# Adafruit_PCF8523_RTC_HVSON.net
KiCad netlist of a schematic drawn in EAGLE
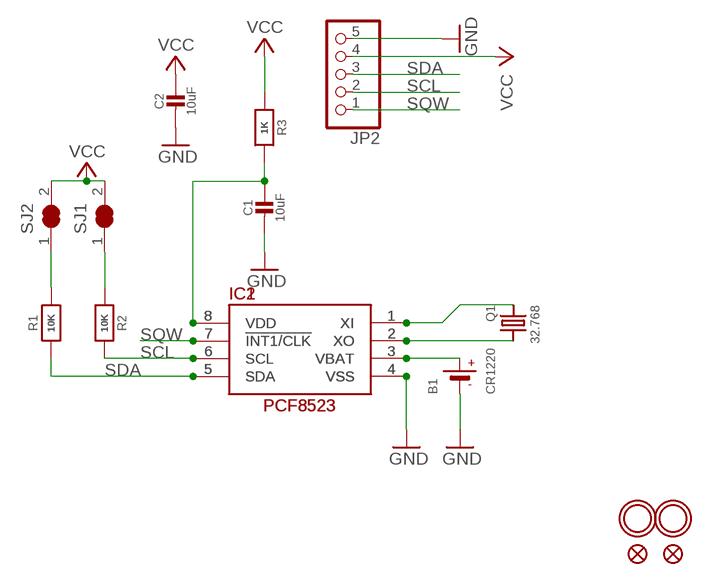
[diagram p0: schematic, sheet 1]

(export (version "E")
  (design (tool "Eeschema 10.0.6"))
  (components
    (comp (ref "B1")
      (value "CR1220")
      (footprint "eagle-import:CR1220")
      (libsource (lib "eagle-import") (part "BATTERYCR1220_SMT"))
    )
    (comp (ref "C1")
      (value "10uF")
      (footprint "eagle-import:0805-NO")
      (libsource (lib "eagle-import") (part "CAP_CERAMIC0805-NOOUTLINE"))
    )
    (comp (ref "C2")
      (value "10uF")
      (footprint "eagle-import:0805-NO")
      (libsource (lib "eagle-import") (part "CAP_CERAMIC0805-NOOUTLINE"))
    )
    (comp (ref "FID1")
      (value "FIDUCIAL_1MM")
      (footprint "eagle-import:FIDUCIAL_1MM")
      (libsource (lib "eagle-import") (part "FIDUCIAL_1MM"))
    )
    (comp (ref "FID2")
      (value "FIDUCIAL_1MM")
      (footprint "eagle-import:FIDUCIAL_1MM")
      (libsource (lib "eagle-import") (part "FIDUCIAL_1MM"))
    )
    (comp (ref "IC1")
      (value "RTC_PCF8523/T")
      (footprint "eagle-import:SOIC8_150MIL")
      (libsource (lib "eagle-import") (part "RTC_PCF8523/T"))
    )
    (comp (ref "IC2")
      (value "RTC_PCF8523/TK")
      (footprint "eagle-import:HVSON8_4X4")
      (libsource (lib "eagle-import") (part "RTC_PCF8523/TK"))
    )
    (comp (ref "JP2")
      (value "HEADER-1X576MIL")
      (footprint "eagle-import:1X05_ROUND_76")
      (libsource (lib "eagle-import") (part "HEADER-1X576MIL"))
    )
    (comp (ref "Q1")
      (value "32.768")
      (footprint "eagle-import:XTAL3215")
      (libsource (lib "eagle-import") (part "CRYSTAL_3215"))
    )
    (comp (ref "R1")
      (value "10K")
      (footprint "eagle-import:0805-NO")
      (libsource (lib "eagle-import") (part "RESISTOR0805_NOOUTLINE"))
    )
    (comp (ref "R2")
      (value "10K")
      (footprint "eagle-import:0805-NO")
      (libsource (lib "eagle-import") (part "RESISTOR0805_NOOUTLINE"))
    )
    (comp (ref "R3")
      (value "1K")
      (footprint "eagle-import:0805-NO")
      (libsource (lib "eagle-import") (part "RESISTOR0805_NOOUTLINE"))
    )
    (comp (ref "SJ1")
      (value "SOLDERJUMPER_CLOSED")
      (footprint "eagle-import:SOLDERJUMPER_CLOSEDWIRE")
      (libsource (lib "eagle-import") (part "SOLDERJUMPER_CLOSED"))
    )
    (comp (ref "SJ2")
      (value "SOLDERJUMPER_CLOSED")
      (footprint "eagle-import:SOLDERJUMPER_CLOSEDWIRE")
      (libsource (lib "eagle-import") (part "SOLDERJUMPER_CLOSED"))
    )
    (comp (ref "U$1")
      (value "MOUNTINGHOLE2.0")
      (footprint "eagle-import:MOUNTINGHOLE_2.0_PLATED")
      (libsource (lib "eagle-import") (part "MOUNTINGHOLE2.0"))
    )
    (comp (ref "U$4")
      (value "MOUNTINGHOLE2.0")
      (footprint "eagle-import:MOUNTINGHOLE_2.0_PLATED")
      (libsource (lib "eagle-import") (part "MOUNTINGHOLE2.0"))
    )
  )
  (nets
    (net (code "1") (name "/SCL") (class "Default")
      (node (ref "IC1") (pin "6") (pinfunction "SCL_6") (pintype "bidirectional"))
      (node (ref "IC2") (pin "6") (pinfunction "SCL_6") (pintype "bidirectional"))
      (node (ref "JP2") (pin "2") (pinfunction "2_2") (pintype "passive"))
      (node (ref "R2") (pin "2") (pinfunction "2_2") (pintype "passive"))
    )
    (net (code "2") (name "/SDA") (class "Default")
      (node (ref "IC1") (pin "5") (pinfunction "SDA_5") (pintype "bidirectional"))
      (node (ref "IC2") (pin "5") (pinfunction "SDA_5") (pintype "bidirectional"))
      (node (ref "JP2") (pin "3") (pinfunction "3_3") (pintype "passive"))
      (node (ref "R1") (pin "1") (pinfunction "1_1") (pintype "passive"))
    )
    (net (code "3") (name "/SQW") (class "Default")
      (node (ref "IC1") (pin "7") (pinfunction "~{INT1/CLK}_7") (pintype "output"))
      (node (ref "IC2") (pin "7") (pinfunction "~{INT1/CLK}_7") (pintype "output"))
      (node (ref "JP2") (pin "1") (pinfunction "1_1") (pintype "passive"))
    )
    (net (code "4") (name "GND") (class "Default")
      (node (ref "B1") (pin "-") (pinfunction "-_-") (pintype "passive"))
      (node (ref "C1") (pin "2") (pinfunction "2_2") (pintype "passive"))
      (node (ref "C2") (pin "2") (pinfunction "2_2") (pintype "passive"))
      (node (ref "IC1") (pin "4") (pinfunction "VSS_4") (pintype "power_in"))
      (node (ref "IC2") (pin "4") (pinfunction "VSS_4") (pintype "power_in"))
      (node (ref "JP2") (pin "5") (pinfunction "5_5") (pintype "passive"))
    )
    (net (code "5") (name "Net-(IC1-VBAT)") (class "Default")
      (node (ref "B1") (pin "+$1") (pinfunction "+_+$1") (pintype "passive"))
      (node (ref "B1") (pin "+$2") (pinfunction "+_+$2") (pintype "passive"))
      (node (ref "IC1") (pin "3") (pinfunction "VBAT_3") (pintype "power_in"))
      (node (ref "IC2") (pin "3") (pinfunction "VBAT_3") (pintype "power_in"))
    )
    (net (code "6") (name "Net-(IC1-VDD)") (class "Default")
      (node (ref "C1") (pin "1") (pinfunction "1_1") (pintype "passive"))
      (node (ref "IC1") (pin "8") (pinfunction "VDD_8") (pintype "power_in"))
      (node (ref "IC2") (pin "8") (pinfunction "VDD_8") (pintype "power_in"))
      (node (ref "R3") (pin "2") (pinfunction "2_2") (pintype "passive"))
    )
    (net (code "7") (name "Net-(IC1-XI)") (class "Default")
      (node (ref "IC1") (pin "1") (pinfunction "XI_1") (pintype "input"))
      (node (ref "IC2") (pin "1") (pinfunction "XI_1") (pintype "input"))
      (node (ref "Q1") (pin "P$1") (pinfunction "1_P$1") (pintype "passive"))
    )
    (net (code "8") (name "Net-(IC1-XO)") (class "Default")
      (node (ref "IC1") (pin "2") (pinfunction "XO_2") (pintype "output"))
      (node (ref "IC2") (pin "2") (pinfunction "XO_2") (pintype "output"))
      (node (ref "Q1") (pin "P$2") (pinfunction "2_P$2") (pintype "passive"))
    )
    (net (code "9") (name "Net-(R1-Pad2)") (class "Default")
      (node (ref "R1") (pin "2") (pinfunction "2_2") (pintype "passive"))
      (node (ref "SJ2") (pin "1") (pinfunction "1_1") (pintype "passive"))
    )
    (net (code "10") (name "Net-(R2-Pad1)") (class "Default")
      (node (ref "R2") (pin "1") (pinfunction "1_1") (pintype "passive"))
      (node (ref "SJ1") (pin "1") (pinfunction "1_1") (pintype "passive"))
    )
    (net (code "11") (name "VCC") (class "Default")
      (node (ref "C2") (pin "1") (pinfunction "1_1") (pintype "passive"))
      (node (ref "JP2") (pin "4") (pinfunction "4_4") (pintype "passive"))
      (node (ref "R3") (pin "1") (pinfunction "1_1") (pintype "passive"))
      (node (ref "SJ1") (pin "2") (pinfunction "2_2") (pintype "passive"))
      (node (ref "SJ2") (pin "2") (pinfunction "2_2") (pintype "passive"))
    )
  )
)
